# POWERBOARD5V_ver2-redo.net
KiCad netlist of a schematic drawn in EAGLE
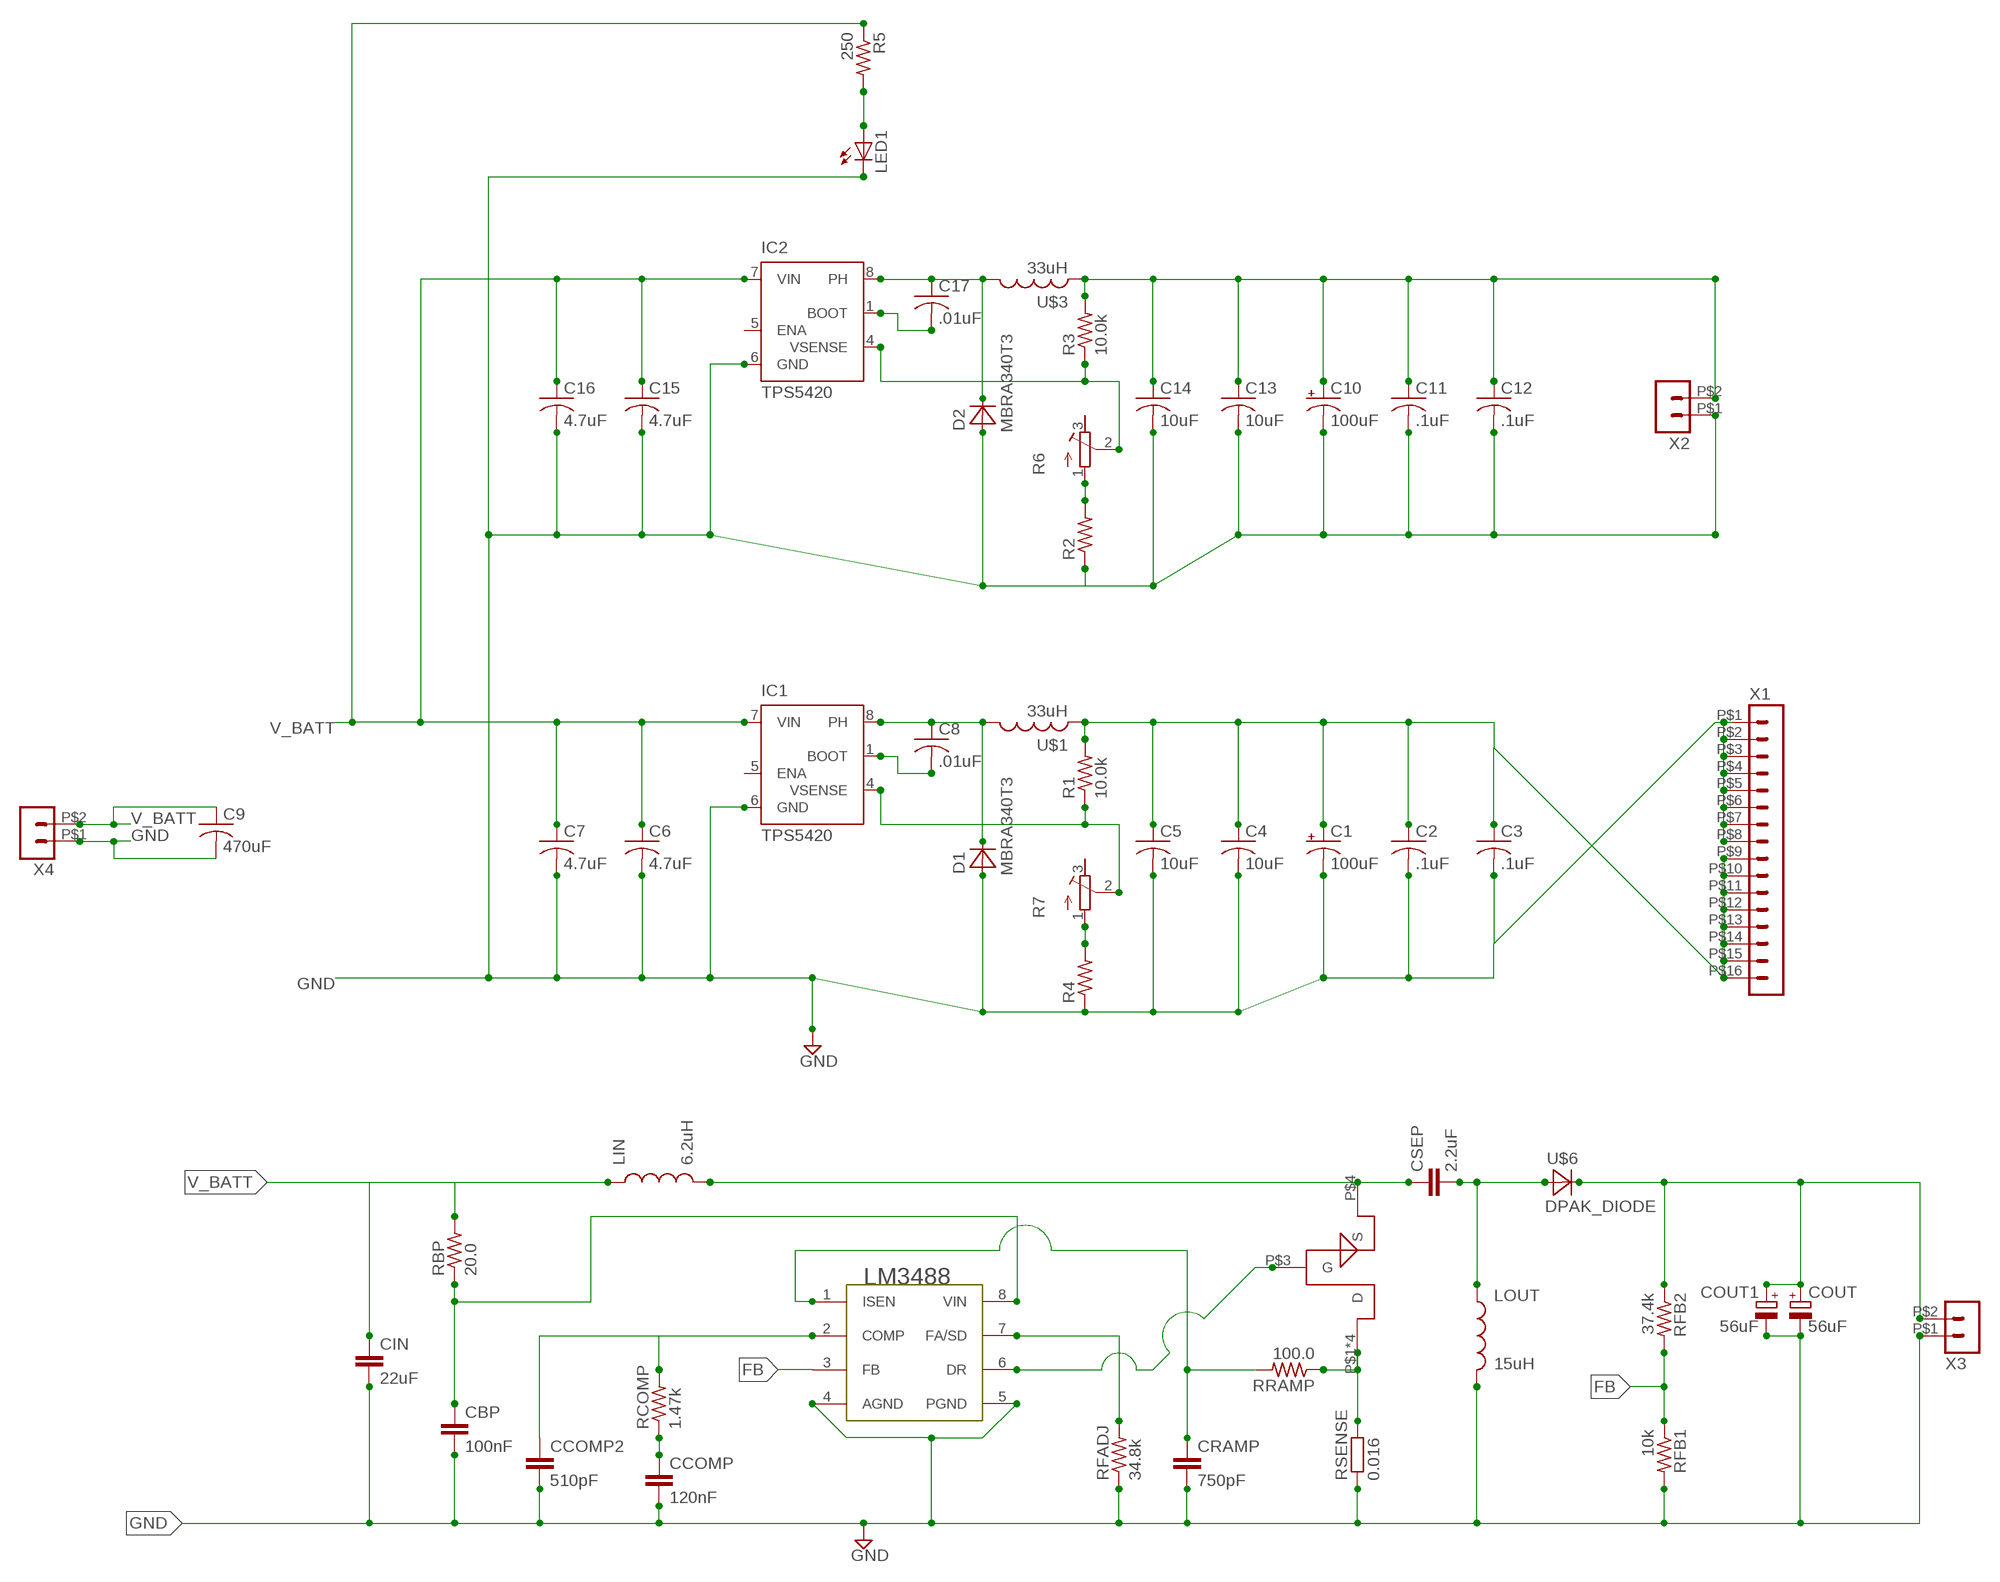
[diagram p0: schematic, sheet 1]

(export (version "E")
  (design (tool "Eeschema 10.0.6"))
  (components
    (comp (ref "C1")
      (value "100uF")
      (footprint "eagle-import:C_6032-28R")
      (libsource (lib "eagle-import") (part "CPOL-USC/6032-28R"))
    )
    (comp (ref "C2")
      (value ".1uF")
      (footprint "eagle-import:C1206K")
      (libsource (lib "eagle-import") (part "C-USC1206K"))
    )
    (comp (ref "C3")
      (value ".1uF")
      (footprint "eagle-import:C1206K")
      (libsource (lib "eagle-import") (part "C-USC1206K"))
    )
    (comp (ref "C4")
      (value "10uF")
      (footprint "eagle-import:C1206K")
      (libsource (lib "eagle-import") (part "C-USC1206K"))
    )
    (comp (ref "C5")
      (value "10uF")
      (footprint "eagle-import:C1206K")
      (libsource (lib "eagle-import") (part "C-USC1206K"))
    )
    (comp (ref "C6")
      (value "4.7uF")
      (footprint "eagle-import:C1812K")
      (libsource (lib "eagle-import") (part "C-USC1812K"))
    )
    (comp (ref "C7")
      (value "4.7uF")
      (footprint "eagle-import:C1812K")
      (libsource (lib "eagle-import") (part "C-USC1812K"))
    )
    (comp (ref "C8")
      (value ".01uF")
      (footprint "eagle-import:C0805K")
      (libsource (lib "eagle-import") (part "C-USC0805K"))
    )
    (comp (ref "C9")
      (value "470uF")
      (footprint "eagle-import:C1812K")
      (libsource (lib "eagle-import") (part "resistor_C-USC1812K"))
    )
    (comp (ref "C10")
      (value "100uF")
      (footprint "eagle-import:C_6032-28R")
      (libsource (lib "eagle-import") (part "CPOL-USC/6032-28R"))
    )
    (comp (ref "C11")
      (value ".1uF")
      (footprint "eagle-import:C1206K")
      (libsource (lib "eagle-import") (part "C-USC1206K"))
    )
    (comp (ref "C12")
      (value ".1uF")
      (footprint "eagle-import:C1206K")
      (libsource (lib "eagle-import") (part "C-USC1206K"))
    )
    (comp (ref "C13")
      (value "10uF")
      (footprint "eagle-import:C1206K")
      (libsource (lib "eagle-import") (part "C-USC1206K"))
    )
    (comp (ref "C14")
      (value "10uF")
      (footprint "eagle-import:C1206K")
      (libsource (lib "eagle-import") (part "C-USC1206K"))
    )
    (comp (ref "C15")
      (value "4.7uF")
      (footprint "eagle-import:C1812K")
      (libsource (lib "eagle-import") (part "C-USC1812K"))
    )
    (comp (ref "C16")
      (value "4.7uF")
      (footprint "eagle-import:C1812K")
      (libsource (lib "eagle-import") (part "C-USC1812K"))
    )
    (comp (ref "C17")
      (value ".01uF")
      (footprint "eagle-import:C0805K")
      (libsource (lib "eagle-import") (part "C-USC0805K"))
    )
    (comp (ref "CBP")
      (value "100nF")
      (footprint "eagle-import:C0805")
      (libsource (lib "eagle-import") (part "C-EUC0805"))
    )
    (comp (ref "CCOMP")
      (value "120nF")
      (footprint "eagle-import:C0805")
      (libsource (lib "eagle-import") (part "C-EUC0805"))
    )
    (comp (ref "CCOMP2")
      (value "510pF")
      (footprint "eagle-import:C0805")
      (libsource (lib "eagle-import") (part "C-EUC0805"))
    )
    (comp (ref "CIN")
      (value "22uF")
      (footprint "eagle-import:C0805")
      (libsource (lib "eagle-import") (part "C-EUC0805"))
    )
    (comp (ref "COUT")
      (value "56uF")
      (footprint "eagle-import:SANYO-OSCON_SMD_A5")
      (libsource (lib "eagle-import") (part "CPOL-EUSANYO_SMD_A5"))
    )
    (comp (ref "COUT1")
      (value "56uF")
      (footprint "eagle-import:SANYO-OSCON_SMD_A5")
      (libsource (lib "eagle-import") (part "CPOL-EUSANYO_SMD_A5"))
    )
    (comp (ref "CRAMP")
      (value "750pF")
      (footprint "eagle-import:C0805")
      (libsource (lib "eagle-import") (part "C-EUC0805"))
    )
    (comp (ref "CSEP")
      (value "2.2uF")
      (footprint "eagle-import:C0805")
      (libsource (lib "eagle-import") (part "C-EUC0805"))
    )
    (comp (ref "D1")
      (value "MBRA340T3")
      (footprint "eagle-import:SMA")
      (libsource (lib "eagle-import") (part "MBRA340T3"))
    )
    (comp (ref "D2")
      (value "MBRA340T3")
      (footprint "eagle-import:SMA")
      (libsource (lib "eagle-import") (part "MBRA340T3"))
    )
    (comp (ref "IC1")
      (value "TPS5420")
      (footprint "eagle-import:D_R-PDSO-G08")
      (fields (field (name "MPN") "TPS5410DR"))
      (libsource (lib "eagle-import") (part "TPS5420"))
    )
    (comp (ref "IC2")
      (value "TPS5420")
      (footprint "eagle-import:D_R-PDSO-G08")
      (fields (field (name "MPN") "TPS5410DR"))
      (libsource (lib "eagle-import") (part "TPS5420"))
    )
    (comp (ref "LED1")
      (value "LEDSML1206")
      (footprint "eagle-import:SML1206")
      (libsource (lib "eagle-import") (part "LEDSML1206"))
    )
    (comp (ref "LIN")
      (value "6.2uH")
      (footprint "eagle-import:SRU1038")
      (libsource (lib "eagle-import") (part "INDUCTORSRU1038"))
    )
    (comp (ref "LOUT")
      (value "15uH")
      (footprint "eagle-import:SRU1038")
      (libsource (lib "eagle-import") (part "INDUCTORSRU1038"))
    )
    (comp (ref "R1")
      (value "10.0k")
      (footprint "eagle-import:R3216")
      (libsource (lib "eagle-import") (part "R-US_R3216"))
    )
    (comp (ref "R2")
      (value "R-US_R3216")
      (footprint "eagle-import:R3216")
      (libsource (lib "eagle-import") (part "R-US_R3216"))
    )
    (comp (ref "R3")
      (value "10.0k")
      (footprint "eagle-import:R3216")
      (libsource (lib "eagle-import") (part "R-US_R3216"))
    )
    (comp (ref "R4")
      (value "R-US_R3216")
      (footprint "eagle-import:R3216")
      (libsource (lib "eagle-import") (part "R-US_R3216"))
    )
    (comp (ref "R5")
      (value "250")
      (footprint "eagle-import:R1206")
      (libsource (lib "eagle-import") (part "R-US_R1206"))
    )
    (comp (ref "R6")
      (value "R-TRIMM3224W")
      (footprint "eagle-import:RTRIM3224W")
      (libsource (lib "eagle-import") (part "R-TRIMM3224W"))
    )
    (comp (ref "R7")
      (value "R-TRIMM3224W")
      (footprint "eagle-import:RTRIM3224W")
      (libsource (lib "eagle-import") (part "R-TRIMM3224W"))
    )
    (comp (ref "RBP")
      (value "20.0")
      (footprint "eagle-import:R0805")
      (libsource (lib "eagle-import") (part "R-US_R0805"))
    )
    (comp (ref "RCOMP")
      (value "1.47k")
      (footprint "eagle-import:R0805")
      (libsource (lib "eagle-import") (part "R-US_R0805"))
    )
    (comp (ref "RFADJ")
      (value "34.8k")
      (footprint "eagle-import:R0805")
      (libsource (lib "eagle-import") (part "R-US_R0805"))
    )
    (comp (ref "RFB1")
      (value "10k")
      (footprint "eagle-import:R0805")
      (libsource (lib "eagle-import") (part "R-US_R0805"))
    )
    (comp (ref "RFB2")
      (value "37.4k")
      (footprint "eagle-import:R0805")
      (libsource (lib "eagle-import") (part "R-US_R0805"))
    )
    (comp (ref "RRAMP")
      (value "100.0")
      (footprint "eagle-import:R0805")
      (libsource (lib "eagle-import") (part "R-US_R0805"))
    )
    (comp (ref "RSENSE")
      (value "0.016")
      (footprint "eagle-import:R2512")
      (libsource (lib "eagle-import") (part "R-EU_R2512"))
    )
    (comp (ref "U$1")
      (value "33uH")
      (footprint "eagle-import:MSS1260")
      (libsource (lib "eagle-import") (part "MSS1260"))
    )
    (comp (ref "U$2")
      (value "LM3488")
      (footprint "eagle-import:SO08")
      (libsource (lib "eagle-import") (part "LM3488"))
    )
    (comp (ref "U$3")
      (value "33uH")
      (footprint "eagle-import:MSS1260")
      (libsource (lib "eagle-import") (part "MSS1260"))
    )
    (comp (ref "U$5")
      (value "P-CHANNEL20V(D-S)MOSFET")
      (footprint "eagle-import:TSOP-6")
      (libsource (lib "eagle-import") (part "P-CHANNEL20V(D-S)MOSFET"))
    )
    (comp (ref "U$6")
      (value "DPAK_DIODE")
      (footprint "eagle-import:DPAK")
      (libsource (lib "eagle-import") (part "DPAK_DIODE"))
    )
    (comp (ref "X1")
      (value "HEADER_POS16_43045-1606")
      (footprint "eagle-import:43045-1606")
      (libsource (lib "eagle-import") (part "HEADER_POS16_?43045-1606"))
    )
    (comp (ref "X2")
      (value "HEADER_POS2_43045-0206")
      (footprint "eagle-import:43045-0206")
      (libsource (lib "eagle-import") (part "HEADER_POS2_?43045-0206"))
    )
    (comp (ref "X3")
      (value "HEADER_POS2_43045-0206")
      (footprint "eagle-import:43045-0206")
      (libsource (lib "eagle-import") (part "HEADER_POS2_?43045-0206"))
    )
    (comp (ref "X4")
      (value "HEADER_POS2_43045-0206")
      (footprint "eagle-import:43045-0206")
      (libsource (lib "eagle-import") (part "HEADER_POS2_?43045-0206"))
    )
  )
  (nets
    (net (code "1") (name "FB") (class "Default")
      (node (ref "RFB1") (pin "1") (pinfunction "1_1") (pintype "passive"))
      (node (ref "RFB2") (pin "2") (pinfunction "2_2") (pintype "passive"))
      (node (ref "U$2") (pin "3") (pinfunction "FB_3") (pintype "bidirectional"))
    )
    (net (code "2") (name "GND") (class "Default")
      (node (ref "C1") (pin "-") (pinfunction "-_-") (pintype "passive"))
      (node (ref "C10") (pin "-") (pinfunction "-_-") (pintype "passive"))
      (node (ref "C11") (pin "2") (pinfunction "2_2") (pintype "passive"))
      (node (ref "C12") (pin "2") (pinfunction "2_2") (pintype "passive"))
      (node (ref "C13") (pin "2") (pinfunction "2_2") (pintype "passive"))
      (node (ref "C14") (pin "2") (pinfunction "2_2") (pintype "passive"))
      (node (ref "C15") (pin "2") (pinfunction "2_2") (pintype "passive"))
      (node (ref "C16") (pin "2") (pinfunction "2_2") (pintype "passive"))
      (node (ref "C2") (pin "2") (pinfunction "2_2") (pintype "passive"))
      (node (ref "C3") (pin "2") (pinfunction "2_2") (pintype "passive"))
      (node (ref "C4") (pin "2") (pinfunction "2_2") (pintype "passive"))
      (node (ref "C5") (pin "2") (pinfunction "2_2") (pintype "passive"))
      (node (ref "C6") (pin "2") (pinfunction "2_2") (pintype "passive"))
      (node (ref "C7") (pin "2") (pinfunction "2_2") (pintype "passive"))
      (node (ref "C9") (pin "2") (pinfunction "2_2") (pintype "passive"))
      (node (ref "CBP") (pin "2") (pinfunction "2_2") (pintype "passive"))
      (node (ref "CCOMP") (pin "2") (pinfunction "2_2") (pintype "passive"))
      (node (ref "CCOMP2") (pin "2") (pinfunction "2_2") (pintype "passive"))
      (node (ref "CIN") (pin "2") (pinfunction "2_2") (pintype "passive"))
      (node (ref "COUT") (pin "-") (pinfunction "-_-") (pintype "passive"))
      (node (ref "COUT1") (pin "-") (pinfunction "-_-") (pintype "passive"))
      (node (ref "CRAMP") (pin "2") (pinfunction "2_2") (pintype "passive"))
      (node (ref "D1") (pin "A") (pinfunction "A_A") (pintype "passive"))
      (node (ref "D2") (pin "A") (pinfunction "A_A") (pintype "passive"))
      (node (ref "IC1") (pin "6") (pinfunction "GND_6") (pintype "power_in"))
      (node (ref "IC2") (pin "6") (pinfunction "GND_6") (pintype "power_in"))
      (node (ref "LED1") (pin "C") (pinfunction "C_C") (pintype "passive"))
      (node (ref "LOUT") (pin "2") (pinfunction "2_2") (pintype "passive"))
      (node (ref "R2") (pin "1") (pinfunction "1_1") (pintype "passive"))
      (node (ref "R4") (pin "1") (pinfunction "1_1") (pintype "passive"))
      (node (ref "RFADJ") (pin "1") (pinfunction "1_1") (pintype "passive"))
      (node (ref "RFB1") (pin "2") (pinfunction "2_2") (pintype "passive"))
      (node (ref "RSENSE") (pin "1") (pinfunction "1_1") (pintype "passive"))
      (node (ref "U$2") (pin "4") (pinfunction "AGND_4") (pintype "bidirectional"))
      (node (ref "U$2") (pin "5") (pinfunction "PGND_5") (pintype "bidirectional"))
      (node (ref "X1") (pin "P$1") (pinfunction "1_P$1") (pintype "passive"))
      (node (ref "X1") (pin "P$2") (pinfunction "2_P$2") (pintype "passive"))
      (node (ref "X1") (pin "P$3") (pinfunction "3_P$3") (pintype "passive"))
      (node (ref "X1") (pin "P$4") (pinfunction "4_P$4") (pintype "passive"))
      (node (ref "X1") (pin "P$5") (pinfunction "5_P$5") (pintype "passive"))
      (node (ref "X1") (pin "P$6") (pinfunction "6_P$6") (pintype "passive"))
      (node (ref "X1") (pin "P$7") (pinfunction "7_P$7") (pintype "passive"))
      (node (ref "X1") (pin "P$8") (pinfunction "8_P$8") (pintype "passive"))
      (node (ref "X2") (pin "P$1") (pinfunction "1_P$1") (pintype "passive"))
      (node (ref "X3") (pin "P$1") (pinfunction "1_P$1") (pintype "passive"))
      (node (ref "X4") (pin "P$1") (pinfunction "1_P$1") (pintype "passive"))
    )
    (net (code "3") (name "Net-(CCOMP-Pad1)") (class "Default")
      (node (ref "CCOMP") (pin "1") (pinfunction "1_1") (pintype "passive"))
      (node (ref "RCOMP") (pin "1") (pinfunction "1_1") (pintype "passive"))
    )
    (net (code "4") (name "Net-(CSEP-Pad2)") (class "Default")
      (node (ref "CSEP") (pin "2") (pinfunction "2_2") (pintype "passive"))
      (node (ref "LOUT") (pin "1") (pinfunction "1_1") (pintype "passive"))
      (node (ref "U$6") (pin "1") (pinfunction "A_1") (pintype "passive"))
      (node (ref "U$6") (pin "3") (pinfunction "A_3") (pintype "passive"))
    )
    (net (code "5") (name "Net-(IC1-BOOT)") (class "Default")
      (node (ref "C8") (pin "2") (pinfunction "2_2") (pintype "passive"))
      (node (ref "IC1") (pin "1") (pinfunction "BOOT_1") (pintype "output"))
    )
    (net (code "6") (name "Net-(IC1-PH)") (class "Default")
      (node (ref "C8") (pin "1") (pinfunction "1_1") (pintype "passive"))
      (node (ref "D1") (pin "C") (pinfunction "C_C") (pintype "passive"))
      (node (ref "IC1") (pin "8") (pinfunction "PH_8") (pintype "output"))
      (node (ref "U$1") (pin "P$1") (pinfunction "P$1_P$1") (pintype "passive"))
      (node (ref "U$1") (pin "P$3") (pinfunction "P$1_P$3") (pintype "passive"))
    )
    (net (code "7") (name "Net-(IC1-VSENSE)") (class "Default")
      (node (ref "IC1") (pin "4") (pinfunction "VSENSE_4") (pintype "input"))
      (node (ref "R1") (pin "1") (pinfunction "1_1") (pintype "passive"))
      (node (ref "R7") (pin "2") (pinfunction "S_2") (pintype "passive"))
    )
    (net (code "8") (name "Net-(IC2-BOOT)") (class "Default")
      (node (ref "C17") (pin "2") (pinfunction "2_2") (pintype "passive"))
      (node (ref "IC2") (pin "1") (pinfunction "BOOT_1") (pintype "output"))
    )
    (net (code "9") (name "Net-(IC2-PH)") (class "Default")
      (node (ref "C17") (pin "1") (pinfunction "1_1") (pintype "passive"))
      (node (ref "D2") (pin "C") (pinfunction "C_C") (pintype "passive"))
      (node (ref "IC2") (pin "8") (pinfunction "PH_8") (pintype "output"))
      (node (ref "U$3") (pin "P$1") (pinfunction "P$1_P$1") (pintype "passive"))
      (node (ref "U$3") (pin "P$3") (pinfunction "P$1_P$3") (pintype "passive"))
    )
    (net (code "10") (name "Net-(IC2-VSENSE)") (class "Default")
      (node (ref "IC2") (pin "4") (pinfunction "VSENSE_4") (pintype "input"))
      (node (ref "R3") (pin "1") (pinfunction "1_1") (pintype "passive"))
      (node (ref "R6") (pin "2") (pinfunction "S_2") (pintype "passive"))
    )
    (net (code "11") (name "Net-(LED1-PadA)") (class "Default")
      (node (ref "LED1") (pin "A") (pinfunction "A_A") (pintype "passive"))
      (node (ref "R5") (pin "2") (pinfunction "2_2") (pintype "passive"))
    )
    (net (code "12") (name "Net-(R6-A)") (class "Default")
      (node (ref "R2") (pin "2") (pinfunction "2_2") (pintype "passive"))
      (node (ref "R6") (pin "1") (pinfunction "A_1") (pintype "passive"))
    )
    (net (code "13") (name "Net-(R7-A)") (class "Default")
      (node (ref "R4") (pin "2") (pinfunction "2_2") (pintype "passive"))
      (node (ref "R7") (pin "1") (pinfunction "A_1") (pintype "passive"))
    )
    (net (code "14") (name "Net-(RRAMP-Pad1)") (class "Default")
      (node (ref "RRAMP") (pin "1") (pinfunction "1_1") (pintype "passive"))
      (node (ref "RSENSE") (pin "2") (pinfunction "2_2") (pintype "passive"))
      (node (ref "U$5") (pin "P$1") (pinfunction "D_P$1") (pintype "bidirectional"))
      (node (ref "U$5") (pin "P$2") (pinfunction "D_P$2") (pintype "bidirectional"))
      (node (ref "U$5") (pin "P$5") (pinfunction "D_P$5") (pintype "bidirectional"))
      (node (ref "U$5") (pin "P$6") (pinfunction "D_P$6") (pintype "bidirectional"))
    )
    (net (code "15") (name "Net-(U$2-COMP)") (class "Default")
      (node (ref "CCOMP2") (pin "1") (pinfunction "1_1") (pintype "passive"))
      (node (ref "RCOMP") (pin "2") (pinfunction "2_2") (pintype "passive"))
      (node (ref "U$2") (pin "2") (pinfunction "COMP_2") (pintype "bidirectional"))
    )
    (net (code "16") (name "Net-(U$2-DR)") (class "Default")
      (node (ref "U$2") (pin "6") (pinfunction "DR_6") (pintype "bidirectional"))
      (node (ref "U$5") (pin "P$3") (pinfunction "G_P$3") (pintype "bidirectional"))
    )
    (net (code "17") (name "Net-(U$2-FA{slash}SD)") (class "Default")
      (node (ref "RFADJ") (pin "2") (pinfunction "2_2") (pintype "passive"))
      (node (ref "U$2") (pin "7") (pinfunction "FA/SD_7") (pintype "bidirectional"))
    )
    (net (code "18") (name "Net-(U$2-ISEN)") (class "Default")
      (node (ref "CRAMP") (pin "1") (pinfunction "1_1") (pintype "passive"))
      (node (ref "RRAMP") (pin "2") (pinfunction "2_2") (pintype "passive"))
      (node (ref "U$2") (pin "1") (pinfunction "ISEN_1") (pintype "bidirectional"))
    )
    (net (code "19") (name "Net-(U$2-VIN)") (class "Default")
      (node (ref "CBP") (pin "1") (pinfunction "1_1") (pintype "passive"))
      (node (ref "RBP") (pin "1") (pinfunction "1_1") (pintype "passive"))
      (node (ref "U$2") (pin "8") (pinfunction "VIN_8") (pintype "bidirectional"))
    )
    (net (code "20") (name "Net-(U$5-S)") (class "Default")
      (node (ref "CSEP") (pin "1") (pinfunction "1_1") (pintype "passive"))
      (node (ref "LIN") (pin "2") (pinfunction "2_2") (pintype "passive"))
      (node (ref "U$5") (pin "P$4") (pinfunction "S_P$4") (pintype "bidirectional"))
    )
    (net (code "21") (name "Net-(U$6-C)") (class "Default")
      (node (ref "COUT") (pin "+") (pinfunction "+_+") (pintype "passive"))
      (node (ref "COUT1") (pin "+") (pinfunction "+_+") (pintype "passive"))
      (node (ref "RFB2") (pin "1") (pinfunction "1_1") (pintype "passive"))
      (node (ref "U$6") (pin "4") (pinfunction "C_4") (pintype "passive"))
      (node (ref "X3") (pin "P$2") (pinfunction "2_P$2") (pintype "passive"))
    )
    (net (code "22") (name "Net-(X1-10)") (class "Default")
      (node (ref "C1") (pin "+") (pinfunction "+_+") (pintype "passive"))
      (node (ref "C2") (pin "1") (pinfunction "1_1") (pintype "passive"))
      (node (ref "C3") (pin "1") (pinfunction "1_1") (pintype "passive"))
      (node (ref "C4") (pin "1") (pinfunction "1_1") (pintype "passive"))
      (node (ref "C5") (pin "1") (pinfunction "1_1") (pintype "passive"))
      (node (ref "R1") (pin "2") (pinfunction "2_2") (pintype "passive"))
      (node (ref "U$1") (pin "P$2") (pinfunction "P$2_P$2") (pintype "passive"))
      (node (ref "U$1") (pin "P$4") (pinfunction "P$2_P$4") (pintype "passive"))
      (node (ref "X1") (pin "P$10") (pinfunction "10_P$10") (pintype "passive"))
      (node (ref "X1") (pin "P$11") (pinfunction "11_P$11") (pintype "passive"))
      (node (ref "X1") (pin "P$12") (pinfunction "12_P$12") (pintype "passive"))
      (node (ref "X1") (pin "P$13") (pinfunction "13_P$13") (pintype "passive"))
      (node (ref "X1") (pin "P$14") (pinfunction "14_P$14") (pintype "passive"))
      (node (ref "X1") (pin "P$15") (pinfunction "15_P$15") (pintype "passive"))
      (node (ref "X1") (pin "P$16") (pinfunction "16_P$16") (pintype "passive"))
      (node (ref "X1") (pin "P$9") (pinfunction "9_P$9") (pintype "passive"))
    )
    (net (code "23") (name "Net-(X2-2)") (class "Default")
      (node (ref "C10") (pin "+") (pinfunction "+_+") (pintype "passive"))
      (node (ref "C11") (pin "1") (pinfunction "1_1") (pintype "passive"))
      (node (ref "C12") (pin "1") (pinfunction "1_1") (pintype "passive"))
      (node (ref "C13") (pin "1") (pinfunction "1_1") (pintype "passive"))
      (node (ref "C14") (pin "1") (pinfunction "1_1") (pintype "passive"))
      (node (ref "R3") (pin "2") (pinfunction "2_2") (pintype "passive"))
      (node (ref "U$3") (pin "P$2") (pinfunction "P$2_P$2") (pintype "passive"))
      (node (ref "U$3") (pin "P$4") (pinfunction "P$2_P$4") (pintype "passive"))
      (node (ref "X2") (pin "P$2") (pinfunction "2_P$2") (pintype "passive"))
    )
    (net (code "24") (name "V_BATT") (class "Default")
      (node (ref "C15") (pin "1") (pinfunction "1_1") (pintype "passive"))
      (node (ref "C16") (pin "1") (pinfunction "1_1") (pintype "passive"))
      (node (ref "C6") (pin "1") (pinfunction "1_1") (pintype "passive"))
      (node (ref "C7") (pin "1") (pinfunction "1_1") (pintype "passive"))
      (node (ref "C9") (pin "1") (pinfunction "1_1") (pintype "passive"))
      (node (ref "CIN") (pin "1") (pinfunction "1_1") (pintype "passive"))
      (node (ref "IC1") (pin "7") (pinfunction "VIN_7") (pintype "input"))
      (node (ref "IC2") (pin "7") (pinfunction "VIN_7") (pintype "input"))
      (node (ref "LIN") (pin "1") (pinfunction "1_1") (pintype "passive"))
      (node (ref "R5") (pin "1") (pinfunction "1_1") (pintype "passive"))
      (node (ref "RBP") (pin "2") (pinfunction "2_2") (pintype "passive"))
      (node (ref "X4") (pin "P$2") (pinfunction "2_P$2") (pintype "passive"))
    )
    (net (code "25") (name "unconnected-(IC1-ENA-Pad5)") (class "Default")
      (node (ref "IC1") (pin "5") (pinfunction "ENA_5") (pintype "input"))
    )
    (net (code "26") (name "unconnected-(IC2-ENA-Pad5)") (class "Default")
      (node (ref "IC2") (pin "5") (pinfunction "ENA_5") (pintype "input"))
    )
    (net (code "27") (name "unconnected-(R6-E-Pad3)") (class "Default")
      (node (ref "R6") (pin "3") (pinfunction "E_3") (pintype "passive"))
    )
    (net (code "28") (name "unconnected-(R7-E-Pad3)") (class "Default")
      (node (ref "R7") (pin "3") (pinfunction "E_3") (pintype "passive"))
    )
  )
)
